# 04_CONNECTOR_OUT_2.net
KiCad netlist of a schematic drawn in Altium Designer
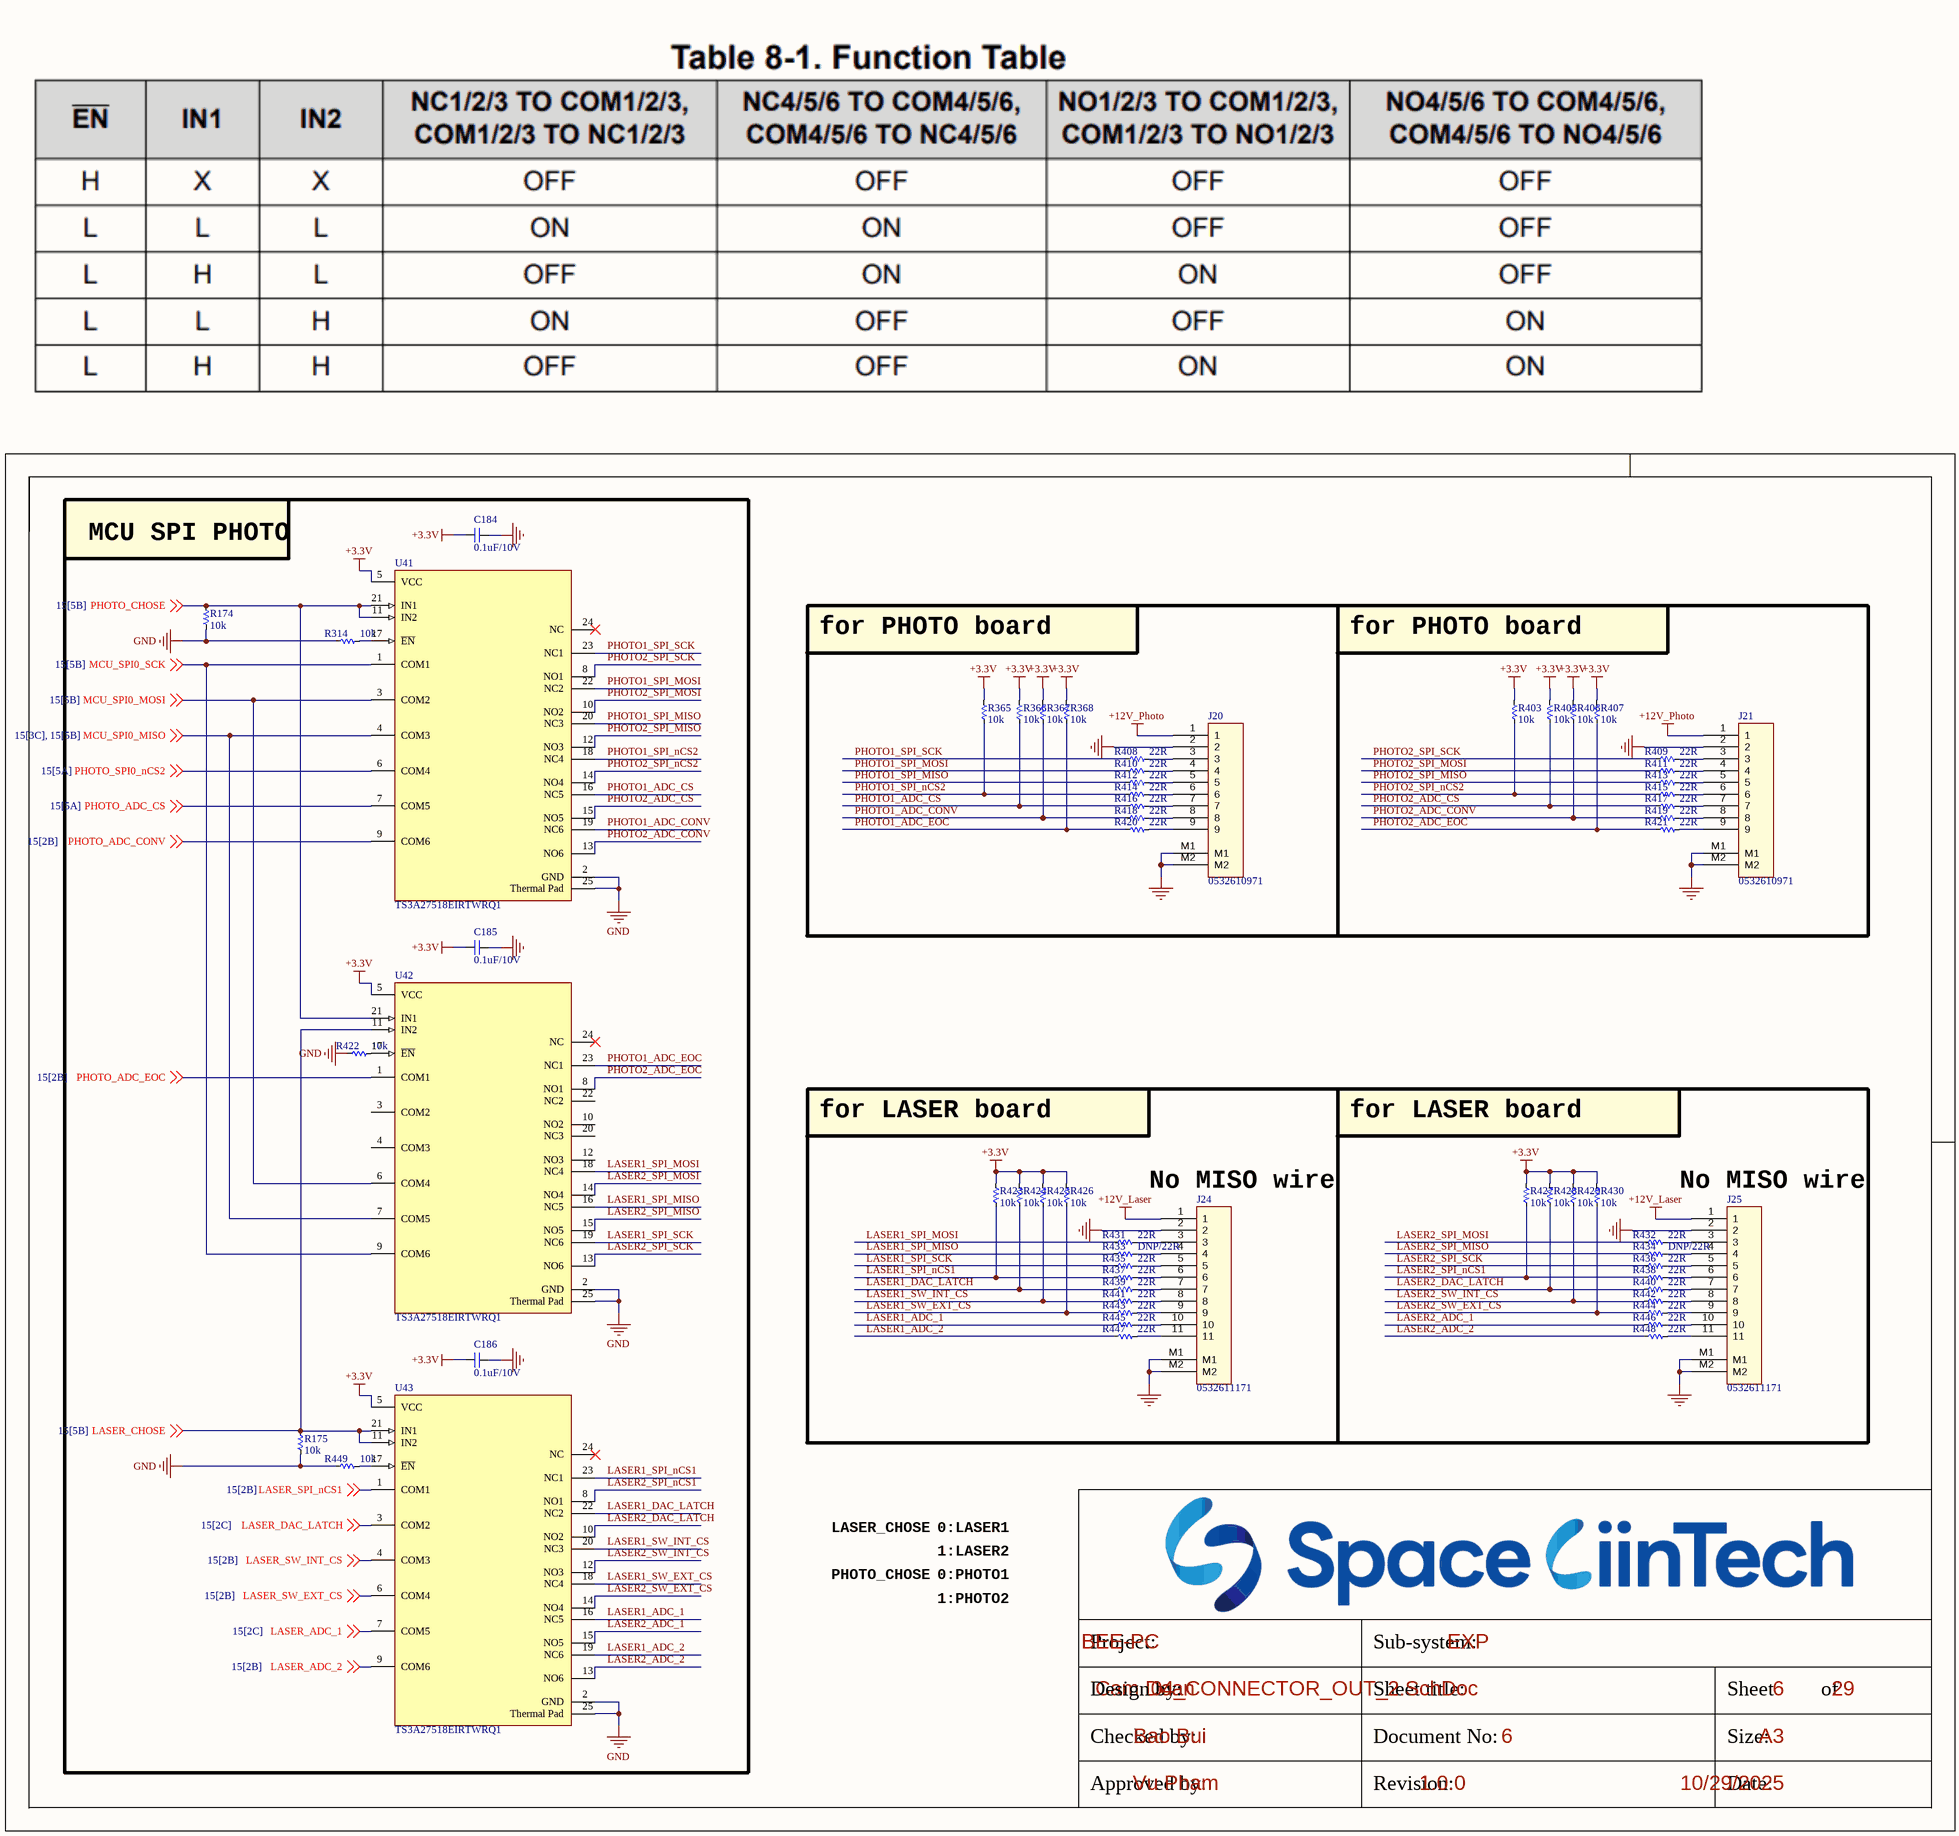
[diagram p0: 04_CONNECTOR_OUT_2.SchDoc]

(export (version "E")
  (design (tool "Eeschema 10.0.6"))
  (components
    (comp (ref "C184")
      (value "0.1uF/10V")
      (footprint "CAP_C_1005X60")
      (description "CAP CHIP")
      (libsource (lib "LABLIB") (part "_CAP_C_2"))
    )
    (comp (ref "C185")
      (value "0.1uF/10V")
      (footprint "CAP_C_1005X60")
      (description "CAP CHIP")
      (libsource (lib "LABLIB") (part "_CAP_C_2"))
    )
    (comp (ref "C186")
      (value "0.1uF/10V")
      (footprint "CAP_C_1005X60")
      (description "CAP CHIP")
      (libsource (lib "LABLIB") (part "_CAP_C_2"))
    )
    (comp (ref "J20")
      (value "0532610971")
      (footprint "MOLEX_0532610971")
      (libsource (lib "LABLIB") (part "Header 9x1_2M"))
    )
    (comp (ref "J21")
      (value "0532610971")
      (footprint "MOLEX_0532610971")
      (libsource (lib "LABLIB") (part "Header 9x1_2M"))
    )
    (comp (ref "J24")
      (value "0532611171")
      (footprint "MOLEX_0532611171")
      (libsource (lib "LABLIB") (part "Header 11x1_2M"))
    )
    (comp (ref "J25")
      (value "0532611171")
      (footprint "MOLEX_0532611171")
      (libsource (lib "LABLIB") (part "Header 11x1_2M"))
    )
    (comp (ref "R174")
      (value "10k")
      (footprint "RES_C_1005X40")
      (description "RES")
      (libsource (lib "LABLIB") (part "_RES_B_2"))
    )
    (comp (ref "R175")
      (value "10k")
      (footprint "RES_C_1005X40")
      (description "RES")
      (libsource (lib "LABLIB") (part "_RES_B_2"))
    )
    (comp (ref "R314")
      (value "10k")
      (footprint "RES_C_1005X40")
      (description "RES")
      (libsource (lib "LABLIB") (part "_RES_B_2"))
    )
    (comp (ref "R365")
      (value "10k")
      (footprint "RES_C_1005X40")
      (description "RES")
      (libsource (lib "LABLIB") (part "_RES_B_2"))
    )
    (comp (ref "R366")
      (value "10k")
      (footprint "RES_C_1005X40")
      (description "RES")
      (libsource (lib "LABLIB") (part "_RES_B_2"))
    )
    (comp (ref "R367")
      (value "10k")
      (footprint "RES_C_1005X40")
      (description "RES")
      (libsource (lib "LABLIB") (part "_RES_B_2"))
    )
    (comp (ref "R368")
      (value "10k")
      (footprint "RES_C_1005X40")
      (description "RES")
      (libsource (lib "LABLIB") (part "_RES_B_2"))
    )
    (comp (ref "R403")
      (value "10k")
      (footprint "RES_C_1005X40")
      (description "RES")
      (libsource (lib "LABLIB") (part "_RES_B_2"))
    )
    (comp (ref "R405")
      (value "10k")
      (footprint "RES_C_1005X40")
      (description "RES")
      (libsource (lib "LABLIB") (part "_RES_B_2"))
    )
    (comp (ref "R406")
      (value "10k")
      (footprint "RES_C_1005X40")
      (description "RES")
      (libsource (lib "LABLIB") (part "_RES_B_2"))
    )
    (comp (ref "R407")
      (value "10k")
      (footprint "RES_C_1005X40")
      (description "RES")
      (libsource (lib "LABLIB") (part "_RES_B_2"))
    )
    (comp (ref "R408")
      (value "22R")
      (footprint "RES_C_1005X40")
      (description "RES")
      (libsource (lib "LABLIB") (part "_RES_B_2"))
    )
    (comp (ref "R409")
      (value "22R")
      (footprint "RES_C_1005X40")
      (description "RES")
      (libsource (lib "LABLIB") (part "_RES_B_2"))
    )
    (comp (ref "R410")
      (value "22R")
      (footprint "RES_C_1005X40")
      (description "RES")
      (libsource (lib "LABLIB") (part "_RES_B_2"))
    )
    (comp (ref "R411")
      (value "22R")
      (footprint "RES_C_1005X40")
      (description "RES")
      (libsource (lib "LABLIB") (part "_RES_B_2"))
    )
    (comp (ref "R412")
      (value "22R")
      (footprint "RES_C_1005X40")
      (description "RES")
      (libsource (lib "LABLIB") (part "_RES_B_2"))
    )
    (comp (ref "R413")
      (value "22R")
      (footprint "RES_C_1005X40")
      (description "RES")
      (libsource (lib "LABLIB") (part "_RES_B_2"))
    )
    (comp (ref "R414")
      (value "22R")
      (footprint "RES_C_1005X40")
      (description "RES")
      (libsource (lib "LABLIB") (part "_RES_B_2"))
    )
    (comp (ref "R415")
      (value "22R")
      (footprint "RES_C_1005X40")
      (description "RES")
      (libsource (lib "LABLIB") (part "_RES_B_2"))
    )
    (comp (ref "R416")
      (value "22R")
      (footprint "RES_C_1005X40")
      (description "RES")
      (libsource (lib "LABLIB") (part "_RES_B_2"))
    )
    (comp (ref "R417")
      (value "22R")
      (footprint "RES_C_1005X40")
      (description "RES")
      (libsource (lib "LABLIB") (part "_RES_B_2"))
    )
    (comp (ref "R418")
      (value "22R")
      (footprint "RES_C_1005X40")
      (description "RES")
      (libsource (lib "LABLIB") (part "_RES_B_2"))
    )
    (comp (ref "R419")
      (value "22R")
      (footprint "RES_C_1005X40")
      (description "RES")
      (libsource (lib "LABLIB") (part "_RES_B_2"))
    )
    (comp (ref "R420")
      (value "22R")
      (footprint "RES_C_1005X40")
      (description "RES")
      (libsource (lib "LABLIB") (part "_RES_B_2"))
    )
    (comp (ref "R421")
      (value "22R")
      (footprint "RES_C_1005X40")
      (description "RES")
      (libsource (lib "LABLIB") (part "_RES_B_2"))
    )
    (comp (ref "R422")
      (value "10k")
      (footprint "RES_C_1005X40")
      (description "RES")
      (libsource (lib "LABLIB") (part "_RES_B_2"))
    )
    (comp (ref "R423")
      (value "10k")
      (footprint "RES_C_1005X40")
      (description "RES")
      (libsource (lib "LABLIB") (part "_RES_B_2"))
    )
    (comp (ref "R424")
      (value "10k")
      (footprint "RES_C_1005X40")
      (description "RES")
      (libsource (lib "LABLIB") (part "_RES_B_2"))
    )
    (comp (ref "R425")
      (value "10k")
      (footprint "RES_C_1005X40")
      (description "RES")
      (libsource (lib "LABLIB") (part "_RES_B_2"))
    )
    (comp (ref "R426")
      (value "10k")
      (footprint "RES_C_1005X40")
      (description "RES")
      (libsource (lib "LABLIB") (part "_RES_B_2"))
    )
    (comp (ref "R427")
      (value "10k")
      (footprint "RES_C_1005X40")
      (description "RES")
      (libsource (lib "LABLIB") (part "_RES_B_2"))
    )
    (comp (ref "R428")
      (value "10k")
      (footprint "RES_C_1005X40")
      (description "RES")
      (libsource (lib "LABLIB") (part "_RES_B_2"))
    )
    (comp (ref "R429")
      (value "10k")
      (footprint "RES_C_1005X40")
      (description "RES")
      (libsource (lib "LABLIB") (part "_RES_B_2"))
    )
    (comp (ref "R430")
      (value "10k")
      (footprint "RES_C_1005X40")
      (description "RES")
      (libsource (lib "LABLIB") (part "_RES_B_2"))
    )
    (comp (ref "R431")
      (value "22R")
      (footprint "RES_C_1005X40")
      (description "RES")
      (libsource (lib "LABLIB") (part "_RES_B_2"))
    )
    (comp (ref "R432")
      (value "22R")
      (footprint "RES_C_1005X40")
      (description "RES")
      (libsource (lib "LABLIB") (part "_RES_B_2"))
    )
    (comp (ref "R433")
      (value "DNP/22R")
      (footprint "RES_C_1005X40")
      (description "RES")
      (libsource (lib "LABLIB") (part "_RES_B_2"))
    )
    (comp (ref "R434")
      (value "DNP/22R")
      (footprint "RES_C_1005X40")
      (description "RES")
      (libsource (lib "LABLIB") (part "_RES_B_2"))
    )
    (comp (ref "R435")
      (value "22R")
      (footprint "RES_C_1005X40")
      (description "RES")
      (libsource (lib "LABLIB") (part "_RES_B_2"))
    )
    (comp (ref "R436")
      (value "22R")
      (footprint "RES_C_1005X40")
      (description "RES")
      (libsource (lib "LABLIB") (part "_RES_B_2"))
    )
    (comp (ref "R437")
      (value "22R")
      (footprint "RES_C_1005X40")
      (description "RES")
      (libsource (lib "LABLIB") (part "_RES_B_2"))
    )
    (comp (ref "R438")
      (value "22R")
      (footprint "RES_C_1005X40")
      (description "RES")
      (libsource (lib "LABLIB") (part "_RES_B_2"))
    )
    (comp (ref "R439")
      (value "22R")
      (footprint "RES_C_1005X40")
      (description "RES")
      (libsource (lib "LABLIB") (part "_RES_B_2"))
    )
    (comp (ref "R440")
      (value "22R")
      (footprint "RES_C_1005X40")
      (description "RES")
      (libsource (lib "LABLIB") (part "_RES_B_2"))
    )
    (comp (ref "R441")
      (value "22R")
      (footprint "RES_C_1005X40")
      (description "RES")
      (libsource (lib "LABLIB") (part "_RES_B_2"))
    )
    (comp (ref "R442")
      (value "22R")
      (footprint "RES_C_1005X40")
      (description "RES")
      (libsource (lib "LABLIB") (part "_RES_B_2"))
    )
    (comp (ref "R443")
      (value "22R")
      (footprint "RES_C_1005X40")
      (description "RES")
      (libsource (lib "LABLIB") (part "_RES_B_2"))
    )
    (comp (ref "R444")
      (value "22R")
      (footprint "RES_C_1005X40")
      (description "RES")
      (libsource (lib "LABLIB") (part "_RES_B_2"))
    )
    (comp (ref "R445")
      (value "22R")
      (footprint "RES_C_1005X40")
      (description "RES")
      (libsource (lib "LABLIB") (part "_RES_B_2"))
    )
    (comp (ref "R446")
      (value "22R")
      (footprint "RES_C_1005X40")
      (description "RES")
      (libsource (lib "LABLIB") (part "_RES_B_2"))
    )
    (comp (ref "R447")
      (value "22R")
      (footprint "RES_C_1005X40")
      (description "RES")
      (libsource (lib "LABLIB") (part "_RES_B_2"))
    )
    (comp (ref "R448")
      (value "22R")
      (footprint "RES_C_1005X40")
      (description "RES")
      (libsource (lib "LABLIB") (part "_RES_B_2"))
    )
    (comp (ref "R449")
      (value "10k")
      (footprint "RES_C_1005X40")
      (description "RES")
      (libsource (lib "LABLIB") (part "_RES_B_2"))
    )
    (comp (ref "U41")
      (value "TS3A27518EIRTWRQ1")
      (footprint "FP-RTW0024B-IPC_A")
      (description "IC MUX/DEMUX 1X2 24WQFN")
      (libsource (lib "Altium Content Vault") (part "ff327f4631d6a819810aeca967572ba"))
    )
    (comp (ref "U42")
      (value "TS3A27518EIRTWRQ1")
      (footprint "FP-RTW0024B-IPC_A")
      (description "IC MUX/DEMUX 1X2 24WQFN")
      (libsource (lib "Altium Content Vault") (part "ff327f4631d6a819810aeca967572ba"))
    )
    (comp (ref "U43")
      (value "TS3A27518EIRTWRQ1")
      (footprint "FP-RTW0024B-IPC_A")
      (description "IC MUX/DEMUX 1X2 24WQFN")
      (libsource (lib "Altium Content Vault") (part "ff327f4631d6a819810aeca967572ba"))
    )
  )
  (nets
    (net (code "1") (name "+3.3V") (class "Default")
      (node (ref "C184") (pin "2") (pinfunction "2_2") (pintype "passive"))
      (node (ref "C185") (pin "2") (pinfunction "2_2") (pintype "passive"))
      (node (ref "C186") (pin "2") (pinfunction "2_2") (pintype "passive"))
      (node (ref "R365") (pin "1") (pinfunction "1_1") (pintype "passive"))
      (node (ref "R366") (pin "1") (pinfunction "1_1") (pintype "passive"))
      (node (ref "R367") (pin "1") (pinfunction "1_1") (pintype "passive"))
      (node (ref "R368") (pin "1") (pinfunction "1_1") (pintype "passive"))
      (node (ref "R403") (pin "1") (pinfunction "1_1") (pintype "passive"))
      (node (ref "R405") (pin "1") (pinfunction "1_1") (pintype "passive"))
      (node (ref "R406") (pin "1") (pinfunction "1_1") (pintype "passive"))
      (node (ref "R407") (pin "1") (pinfunction "1_1") (pintype "passive"))
      (node (ref "R423") (pin "1") (pinfunction "1_1") (pintype "passive"))
      (node (ref "R424") (pin "1") (pinfunction "1_1") (pintype "passive"))
      (node (ref "R425") (pin "1") (pinfunction "1_1") (pintype "passive"))
      (node (ref "R426") (pin "1") (pinfunction "1_1") (pintype "passive"))
      (node (ref "R427") (pin "1") (pinfunction "1_1") (pintype "passive"))
      (node (ref "R428") (pin "1") (pinfunction "1_1") (pintype "passive"))
      (node (ref "R429") (pin "1") (pinfunction "1_1") (pintype "passive"))
      (node (ref "R430") (pin "1") (pinfunction "1_1") (pintype "passive"))
      (node (ref "U41") (pin "5") (pinfunction "VCC_5") (pintype "power_in"))
      (node (ref "U42") (pin "5") (pinfunction "VCC_5") (pintype "power_in"))
      (node (ref "U43") (pin "5") (pinfunction "VCC_5") (pintype "power_in"))
    )
    (net (code "2") (name "+12V_Laser") (class "Default")
      (node (ref "J24") (pin "1") (pinfunction "1_1") (pintype "passive"))
      (node (ref "J25") (pin "1") (pinfunction "1_1") (pintype "passive"))
    )
    (net (code "3") (name "+12V_Photo") (class "Default")
      (node (ref "J20") (pin "1") (pinfunction "1_1") (pintype "passive"))
      (node (ref "J21") (pin "1") (pinfunction "1_1") (pintype "passive"))
    )
    (net (code "4") (name "/LASER1_ADC_1") (class "Default")
      (node (ref "R445") (pin "1") (pinfunction "1_1") (pintype "passive"))
      (node (ref "U43") (pin "16") (pinfunction "NC5_16") (pintype "passive"))
    )
    (net (code "5") (name "/LASER1_ADC_2") (class "Default")
      (node (ref "R447") (pin "1") (pinfunction "1_1") (pintype "passive"))
      (node (ref "U43") (pin "19") (pinfunction "NC6_19") (pintype "passive"))
    )
    (net (code "6") (name "/LASER1_DAC_LATCH") (class "Default")
      (node (ref "R424") (pin "2") (pinfunction "2_2") (pintype "passive"))
      (node (ref "R439") (pin "1") (pinfunction "1_1") (pintype "passive"))
      (node (ref "U43") (pin "22") (pinfunction "NC2_22") (pintype "passive"))
    )
    (net (code "7") (name "/LASER1_SPI_MISO") (class "Default")
      (node (ref "R433") (pin "1") (pinfunction "1_1") (pintype "passive"))
      (node (ref "U42") (pin "16") (pinfunction "NC5_16") (pintype "passive"))
    )
    (net (code "8") (name "/LASER1_SPI_MOSI") (class "Default")
      (node (ref "R431") (pin "1") (pinfunction "1_1") (pintype "passive"))
      (node (ref "U42") (pin "18") (pinfunction "NC4_18") (pintype "passive"))
    )
    (net (code "9") (name "/LASER1_SPI_SCK") (class "Default")
      (node (ref "R435") (pin "1") (pinfunction "1_1") (pintype "passive"))
      (node (ref "U42") (pin "19") (pinfunction "NC6_19") (pintype "passive"))
    )
    (net (code "10") (name "/LASER1_SPI_nCS1") (class "Default")
      (node (ref "R423") (pin "2") (pinfunction "2_2") (pintype "passive"))
      (node (ref "R437") (pin "1") (pinfunction "1_1") (pintype "passive"))
      (node (ref "U43") (pin "23") (pinfunction "NC1_23") (pintype "passive"))
    )
    (net (code "11") (name "/LASER1_SW_EXT_CS") (class "Default")
      (node (ref "R426") (pin "2") (pinfunction "2_2") (pintype "passive"))
      (node (ref "R443") (pin "1") (pinfunction "1_1") (pintype "passive"))
      (node (ref "U43") (pin "18") (pinfunction "NC4_18") (pintype "passive"))
    )
    (net (code "12") (name "/LASER1_SW_INT_CS") (class "Default")
      (node (ref "R425") (pin "2") (pinfunction "2_2") (pintype "passive"))
      (node (ref "R441") (pin "1") (pinfunction "1_1") (pintype "passive"))
      (node (ref "U43") (pin "20") (pinfunction "NC3_20") (pintype "passive"))
    )
    (net (code "13") (name "/LASER2_ADC_1") (class "Default")
      (node (ref "R446") (pin "1") (pinfunction "1_1") (pintype "passive"))
      (node (ref "U43") (pin "15") (pinfunction "NO5_15") (pintype "passive"))
    )
    (net (code "14") (name "/LASER2_ADC_2") (class "Default")
      (node (ref "R448") (pin "1") (pinfunction "1_1") (pintype "passive"))
      (node (ref "U43") (pin "13") (pinfunction "NO6_13") (pintype "passive"))
    )
    (net (code "15") (name "/LASER2_DAC_LATCH") (class "Default")
      (node (ref "R428") (pin "2") (pinfunction "2_2") (pintype "passive"))
      (node (ref "R440") (pin "1") (pinfunction "1_1") (pintype "passive"))
      (node (ref "U43") (pin "10") (pinfunction "NO2_10") (pintype "passive"))
    )
    (net (code "16") (name "/LASER2_SPI_MISO") (class "Default")
      (node (ref "R434") (pin "1") (pinfunction "1_1") (pintype "passive"))
      (node (ref "U42") (pin "15") (pinfunction "NO5_15") (pintype "passive"))
    )
    (net (code "17") (name "/LASER2_SPI_MOSI") (class "Default")
      (node (ref "R432") (pin "1") (pinfunction "1_1") (pintype "passive"))
      (node (ref "U42") (pin "14") (pinfunction "NO4_14") (pintype "passive"))
    )
    (net (code "18") (name "/LASER2_SPI_SCK") (class "Default")
      (node (ref "R436") (pin "1") (pinfunction "1_1") (pintype "passive"))
      (node (ref "U42") (pin "13") (pinfunction "NO6_13") (pintype "passive"))
    )
    (net (code "19") (name "/LASER2_SPI_nCS1") (class "Default")
      (node (ref "R427") (pin "2") (pinfunction "2_2") (pintype "passive"))
      (node (ref "R438") (pin "1") (pinfunction "1_1") (pintype "passive"))
      (node (ref "U43") (pin "8") (pinfunction "NO1_8") (pintype "passive"))
    )
    (net (code "20") (name "/LASER2_SW_EXT_CS") (class "Default")
      (node (ref "R430") (pin "2") (pinfunction "2_2") (pintype "passive"))
      (node (ref "R444") (pin "1") (pinfunction "1_1") (pintype "passive"))
      (node (ref "U43") (pin "14") (pinfunction "NO4_14") (pintype "passive"))
    )
    (net (code "21") (name "/LASER2_SW_INT_CS") (class "Default")
      (node (ref "R429") (pin "2") (pinfunction "2_2") (pintype "passive"))
      (node (ref "R442") (pin "1") (pinfunction "1_1") (pintype "passive"))
      (node (ref "U43") (pin "12") (pinfunction "NO3_12") (pintype "passive"))
    )
    (net (code "22") (name "/PHOTO1_ADC_CONV") (class "Default")
      (node (ref "R367") (pin "2") (pinfunction "2_2") (pintype "passive"))
      (node (ref "R418") (pin "1") (pinfunction "1_1") (pintype "passive"))
      (node (ref "U41") (pin "19") (pinfunction "NC6_19") (pintype "passive"))
    )
    (net (code "23") (name "/PHOTO1_ADC_CS") (class "Default")
      (node (ref "R366") (pin "2") (pinfunction "2_2") (pintype "passive"))
      (node (ref "R416") (pin "1") (pinfunction "1_1") (pintype "passive"))
      (node (ref "U41") (pin "16") (pinfunction "NC5_16") (pintype "passive"))
    )
    (net (code "24") (name "/PHOTO1_ADC_EOC") (class "Default")
      (node (ref "R368") (pin "2") (pinfunction "2_2") (pintype "passive"))
      (node (ref "R420") (pin "1") (pinfunction "1_1") (pintype "passive"))
      (node (ref "U42") (pin "23") (pinfunction "NC1_23") (pintype "passive"))
    )
    (net (code "25") (name "/PHOTO1_SPI_MISO") (class "Default")
      (node (ref "R412") (pin "1") (pinfunction "1_1") (pintype "passive"))
      (node (ref "U41") (pin "20") (pinfunction "NC3_20") (pintype "passive"))
    )
    (net (code "26") (name "/PHOTO1_SPI_MOSI") (class "Default")
      (node (ref "R410") (pin "1") (pinfunction "1_1") (pintype "passive"))
      (node (ref "U41") (pin "22") (pinfunction "NC2_22") (pintype "passive"))
    )
    (net (code "27") (name "/PHOTO1_SPI_SCK") (class "Default")
      (node (ref "R408") (pin "1") (pinfunction "1_1") (pintype "passive"))
      (node (ref "U41") (pin "23") (pinfunction "NC1_23") (pintype "passive"))
    )
    (net (code "28") (name "/PHOTO1_SPI_nCS2") (class "Default")
      (node (ref "R365") (pin "2") (pinfunction "2_2") (pintype "passive"))
      (node (ref "R414") (pin "1") (pinfunction "1_1") (pintype "passive"))
      (node (ref "U41") (pin "18") (pinfunction "NC4_18") (pintype "passive"))
    )
    (net (code "29") (name "/PHOTO2_ADC_CONV") (class "Default")
      (node (ref "R406") (pin "2") (pinfunction "2_2") (pintype "passive"))
      (node (ref "R419") (pin "1") (pinfunction "1_1") (pintype "passive"))
      (node (ref "U41") (pin "13") (pinfunction "NO6_13") (pintype "passive"))
    )
    (net (code "30") (name "/PHOTO2_ADC_CS") (class "Default")
      (node (ref "R405") (pin "2") (pinfunction "2_2") (pintype "passive"))
      (node (ref "R417") (pin "1") (pinfunction "1_1") (pintype "passive"))
      (node (ref "U41") (pin "15") (pinfunction "NO5_15") (pintype "passive"))
    )
    (net (code "31") (name "/PHOTO2_ADC_EOC") (class "Default")
      (node (ref "R407") (pin "2") (pinfunction "2_2") (pintype "passive"))
      (node (ref "R421") (pin "1") (pinfunction "1_1") (pintype "passive"))
      (node (ref "U42") (pin "8") (pinfunction "NO1_8") (pintype "passive"))
    )
    (net (code "32") (name "/PHOTO2_SPI_MISO") (class "Default")
      (node (ref "R413") (pin "1") (pinfunction "1_1") (pintype "passive"))
      (node (ref "U41") (pin "12") (pinfunction "NO3_12") (pintype "passive"))
    )
    (net (code "33") (name "/PHOTO2_SPI_MOSI") (class "Default")
      (node (ref "R411") (pin "1") (pinfunction "1_1") (pintype "passive"))
      (node (ref "U41") (pin "10") (pinfunction "NO2_10") (pintype "passive"))
    )
    (net (code "34") (name "/PHOTO2_SPI_SCK") (class "Default")
      (node (ref "R409") (pin "1") (pinfunction "1_1") (pintype "passive"))
      (node (ref "U41") (pin "8") (pinfunction "NO1_8") (pintype "passive"))
    )
    (net (code "35") (name "/PHOTO2_SPI_nCS2") (class "Default")
      (node (ref "R403") (pin "2") (pinfunction "2_2") (pintype "passive"))
      (node (ref "R415") (pin "1") (pinfunction "1_1") (pintype "passive"))
      (node (ref "U41") (pin "14") (pinfunction "NO4_14") (pintype "passive"))
    )
    (net (code "36") (name "GND") (class "Default")
      (node (ref "C184") (pin "1") (pinfunction "1_1") (pintype "passive"))
      (node (ref "C185") (pin "1") (pinfunction "1_1") (pintype "passive"))
      (node (ref "C186") (pin "1") (pinfunction "1_1") (pintype "passive"))
      (node (ref "J20") (pin "2") (pinfunction "2_2") (pintype "passive"))
      (node (ref "J20") (pin "M1") (pinfunction "M1_M1") (pintype "passive"))
      (node (ref "J20") (pin "M2") (pinfunction "M2_M2") (pintype "passive"))
      (node (ref "J21") (pin "2") (pinfunction "2_2") (pintype "passive"))
      (node (ref "J21") (pin "M1") (pinfunction "M1_M1") (pintype "passive"))
      (node (ref "J21") (pin "M2") (pinfunction "M2_M2") (pintype "passive"))
      (node (ref "J24") (pin "2") (pinfunction "2_2") (pintype "passive"))
      (node (ref "J24") (pin "M1") (pinfunction "M1_M1") (pintype "passive"))
      (node (ref "J24") (pin "M2") (pinfunction "M2_M2") (pintype "passive"))
      (node (ref "J25") (pin "2") (pinfunction "2_2") (pintype "passive"))
      (node (ref "J25") (pin "M1") (pinfunction "M1_M1") (pintype "passive"))
      (node (ref "J25") (pin "M2") (pinfunction "M2_M2") (pintype "passive"))
      (node (ref "R174") (pin "1") (pinfunction "1_1") (pintype "passive"))
      (node (ref "R175") (pin "1") (pinfunction "1_1") (pintype "passive"))
      (node (ref "R314") (pin "1") (pinfunction "1_1") (pintype "passive"))
      (node (ref "R422") (pin "1") (pinfunction "1_1") (pintype "passive"))
      (node (ref "R449") (pin "1") (pinfunction "1_1") (pintype "passive"))
      (node (ref "U41") (pin "2") (pinfunction "GND_2") (pintype "power_in"))
      (node (ref "U41") (pin "25") (pinfunction "Thermal_Pad_25") (pintype "power_in"))
      (node (ref "U42") (pin "2") (pinfunction "GND_2") (pintype "power_in"))
      (node (ref "U42") (pin "25") (pinfunction "Thermal_Pad_25") (pintype "power_in"))
      (node (ref "U43") (pin "2") (pinfunction "GND_2") (pintype "power_in"))
      (node (ref "U43") (pin "25") (pinfunction "Thermal_Pad_25") (pintype "power_in"))
    )
    (net (code "37") (name "LASER_ADC_1") (class "Default")
      (node (ref "U43") (pin "7") (pinfunction "COM5_7") (pintype "passive"))
    )
    (net (code "38") (name "LASER_ADC_2") (class "Default")
      (node (ref "U43") (pin "9") (pinfunction "COM6_9") (pintype "passive"))
    )
    (net (code "39") (name "LASER_CHOSE") (class "Default")
      (node (ref "R175") (pin "2") (pinfunction "2_2") (pintype "passive"))
      (node (ref "U42") (pin "11") (pinfunction "IN2_11") (pintype "input"))
      (node (ref "U43") (pin "11") (pinfunction "IN2_11") (pintype "input"))
      (node (ref "U43") (pin "21") (pinfunction "IN1_21") (pintype "input"))
    )
    (net (code "40") (name "LASER_DAC_LATCH") (class "Default")
      (node (ref "U43") (pin "3") (pinfunction "COM2_3") (pintype "passive"))
    )
    (net (code "41") (name "LASER_SPI_nCS1") (class "Default")
      (node (ref "U43") (pin "1") (pinfunction "COM1_1") (pintype "passive"))
    )
    (net (code "42") (name "LASER_SW_EXT_CS") (class "Default")
      (node (ref "U43") (pin "6") (pinfunction "COM4_6") (pintype "passive"))
    )
    (net (code "43") (name "LASER_SW_INT_CS") (class "Default")
      (node (ref "U43") (pin "4") (pinfunction "COM3_4") (pintype "passive"))
    )
    (net (code "44") (name "MCU_SPI0_MISO") (class "Default")
      (node (ref "U41") (pin "4") (pinfunction "COM3_4") (pintype "passive"))
      (node (ref "U42") (pin "7") (pinfunction "COM5_7") (pintype "passive"))
    )
    (net (code "45") (name "MCU_SPI0_MOSI") (class "Default")
      (node (ref "U41") (pin "3") (pinfunction "COM2_3") (pintype "passive"))
      (node (ref "U42") (pin "6") (pinfunction "COM4_6") (pintype "passive"))
    )
    (net (code "46") (name "MCU_SPI0_SCK") (class "Default")
      (node (ref "U41") (pin "1") (pinfunction "COM1_1") (pintype "passive"))
      (node (ref "U42") (pin "9") (pinfunction "COM6_9") (pintype "passive"))
    )
    (net (code "47") (name "Net-(J20-Pad3)") (class "Default")
      (node (ref "J20") (pin "3") (pinfunction "3_3") (pintype "passive"))
      (node (ref "R408") (pin "2") (pinfunction "2_2") (pintype "passive"))
    )
    (net (code "48") (name "Net-(J20-Pad4)") (class "Default")
      (node (ref "J20") (pin "4") (pinfunction "4_4") (pintype "passive"))
      (node (ref "R410") (pin "2") (pinfunction "2_2") (pintype "passive"))
    )
    (net (code "49") (name "Net-(J20-Pad5)") (class "Default")
      (node (ref "J20") (pin "5") (pinfunction "5_5") (pintype "passive"))
      (node (ref "R412") (pin "2") (pinfunction "2_2") (pintype "passive"))
    )
    (net (code "50") (name "Net-(J20-Pad6)") (class "Default")
      (node (ref "J20") (pin "6") (pinfunction "6_6") (pintype "passive"))
      (node (ref "R414") (pin "2") (pinfunction "2_2") (pintype "passive"))
    )
    (net (code "51") (name "Net-(J20-Pad7)") (class "Default")
      (node (ref "J20") (pin "7") (pinfunction "7_7") (pintype "passive"))
      (node (ref "R416") (pin "2") (pinfunction "2_2") (pintype "passive"))
    )
    (net (code "52") (name "Net-(J20-Pad8)") (class "Default")
      (node (ref "J20") (pin "8") (pinfunction "8_8") (pintype "passive"))
      (node (ref "R418") (pin "2") (pinfunction "2_2") (pintype "passive"))
    )
    (net (code "53") (name "Net-(J20-Pad9)") (class "Default")
      (node (ref "J20") (pin "9") (pinfunction "9_9") (pintype "passive"))
      (node (ref "R420") (pin "2") (pinfunction "2_2") (pintype "passive"))
    )
    (net (code "54") (name "Net-(J21-Pad3)") (class "Default")
      (node (ref "J21") (pin "3") (pinfunction "3_3") (pintype "passive"))
      (node (ref "R409") (pin "2") (pinfunction "2_2") (pintype "passive"))
    )
    (net (code "55") (name "Net-(J21-Pad4)") (class "Default")
      (node (ref "J21") (pin "4") (pinfunction "4_4") (pintype "passive"))
      (node (ref "R411") (pin "2") (pinfunction "2_2") (pintype "passive"))
    )
    (net (code "56") (name "Net-(J21-Pad5)") (class "Default")
      (node (ref "J21") (pin "5") (pinfunction "5_5") (pintype "passive"))
      (node (ref "R413") (pin "2") (pinfunction "2_2") (pintype "passive"))
    )
    (net (code "57") (name "Net-(J21-Pad6)") (class "Default")
      (node (ref "J21") (pin "6") (pinfunction "6_6") (pintype "passive"))
      (node (ref "R415") (pin "2") (pinfunction "2_2") (pintype "passive"))
    )
    (net (code "58") (name "Net-(J21-Pad7)") (class "Default")
      (node (ref "J21") (pin "7") (pinfunction "7_7") (pintype "passive"))
      (node (ref "R417") (pin "2") (pinfunction "2_2") (pintype "passive"))
    )
    (net (code "59") (name "Net-(J21-Pad8)") (class "Default")
      (node (ref "J21") (pin "8") (pinfunction "8_8") (pintype "passive"))
      (node (ref "R419") (pin "2") (pinfunction "2_2") (pintype "passive"))
    )
    (net (code "60") (name "Net-(J21-Pad9)") (class "Default")
      (node (ref "J21") (pin "9") (pinfunction "9_9") (pintype "passive"))
      (node (ref "R421") (pin "2") (pinfunction "2_2") (pintype "passive"))
    )
    (net (code "61") (name "Net-(J24-Pad3)") (class "Default")
      (node (ref "J24") (pin "3") (pinfunction "3_3") (pintype "passive"))
      (node (ref "R431") (pin "2") (pinfunction "2_2") (pintype "passive"))
    )
    (net (code "62") (name "Net-(J24-Pad4)") (class "Default")
      (node (ref "J24") (pin "4") (pinfunction "4_4") (pintype "passive"))
      (node (ref "R433") (pin "2") (pinfunction "2_2") (pintype "passive"))
    )
    (net (code "63") (name "Net-(J24-Pad5)") (class "Default")
      (node (ref "J24") (pin "5") (pinfunction "5_5") (pintype "passive"))
      (node (ref "R435") (pin "2") (pinfunction "2_2") (pintype "passive"))
    )
    (net (code "64") (name "Net-(J24-Pad6)") (class "Default")
      (node (ref "J24") (pin "6") (pinfunction "6_6") (pintype "passive"))
      (node (ref "R437") (pin "2") (pinfunction "2_2") (pintype "passive"))
    )
    (net (code "65") (name "Net-(J24-Pad7)") (class "Default")
      (node (ref "J24") (pin "7") (pinfunction "7_7") (pintype "passive"))
      (node (ref "R439") (pin "2") (pinfunction "2_2") (pintype "passive"))
    )
    (net (code "66") (name "Net-(J24-Pad8)") (class "Default")
      (node (ref "J24") (pin "8") (pinfunction "8_8") (pintype "passive"))
      (node (ref "R441") (pin "2") (pinfunction "2_2") (pintype "passive"))
    )
    (net (code "67") (name "Net-(J24-Pad9)") (class "Default")
      (node (ref "J24") (pin "9") (pinfunction "9_9") (pintype "passive"))
      (node (ref "R443") (pin "2") (pinfunction "2_2") (pintype "passive"))
    )
    (net (code "68") (name "Net-(J24-Pad10)") (class "Default")
      (node (ref "J24") (pin "10") (pinfunction "10_10") (pintype "passive"))
      (node (ref "R445") (pin "2") (pinfunction "2_2") (pintype "passive"))
    )
    (net (code "69") (name "Net-(J24-Pad11)") (class "Default")
      (node (ref "J24") (pin "11") (pinfunction "11_11") (pintype "passive"))
      (node (ref "R447") (pin "2") (pinfunction "2_2") (pintype "passive"))
    )
    (net (code "70") (name "Net-(J25-Pad3)") (class "Default")
      (node (ref "J25") (pin "3") (pinfunction "3_3") (pintype "passive"))
      (node (ref "R432") (pin "2") (pinfunction "2_2") (pintype "passive"))
    )
    (net (code "71") (name "Net-(J25-Pad4)") (class "Default")
      (node (ref "J25") (pin "4") (pinfunction "4_4") (pintype "passive"))
      (node (ref "R434") (pin "2") (pinfunction "2_2") (pintype "passive"))
    )
    (net (code "72") (name "Net-(J25-Pad5)") (class "Default")
      (node (ref "J25") (pin "5") (pinfunction "5_5") (pintype "passive"))
      (node (ref "R436") (pin "2") (pinfunction "2_2") (pintype "passive"))
    )
    (net (code "73") (name "Net-(J25-Pad6)") (class "Default")
      (node (ref "J25") (pin "6") (pinfunction "6_6") (pintype "passive"))
      (node (ref "R438") (pin "2") (pinfunction "2_2") (pintype "passive"))
    )
    (net (code "74") (name "Net-(J25-Pad7)") (class "Default")
      (node (ref "J25") (pin "7") (pinfunction "7_7") (pintype "passive"))
      (node (ref "R440") (pin "2") (pinfunction "2_2") (pintype "passive"))
    )
    (net (code "75") (name "Net-(J25-Pad8)") (class "Default")
      (node (ref "J25") (pin "8") (pinfunction "8_8") (pintype "passive"))
      (node (ref "R442") (pin "2") (pinfunction "2_2") (pintype "passive"))
    )
    (net (code "76") (name "Net-(J25-Pad9)") (class "Default")
      (node (ref "J25") (pin "9") (pinfunction "9_9") (pintype "passive"))
      (node (ref "R444") (pin "2") (pinfunction "2_2") (pintype "passive"))
    )
    (net (code "77") (name "Net-(J25-Pad10)") (class "Default")
      (node (ref "J25") (pin "10") (pinfunction "10_10") (pintype "passive"))
      (node (ref "R446") (pin "2") (pinfunction "2_2") (pintype "passive"))
    )
    (net (code "78") (name "Net-(J25-Pad11)") (class "Default")
      (node (ref "J25") (pin "11") (pinfunction "11_11") (pintype "passive"))
      (node (ref "R448") (pin "2") (pinfunction "2_2") (pintype "passive"))
    )
    (net (code "79") (name "Net-(U41-~{EN})") (class "Default")
      (node (ref "R314") (pin "2") (pinfunction "2_2") (pintype "passive"))
      (node (ref "U41") (pin "17") (pinfunction "~{EN}_17") (pintype "input"))
    )
    (net (code "80") (name "Net-(U42-~{EN})") (class "Default")
      (node (ref "R422") (pin "2") (pinfunction "2_2") (pintype "passive"))
      (node (ref "U42") (pin "17") (pinfunction "~{EN}_17") (pintype "input"))
    )
    (net (code "81") (name "Net-(U43-~{EN})") (class "Default")
      (node (ref "R449") (pin "2") (pinfunction "2_2") (pintype "passive"))
      (node (ref "U43") (pin "17") (pinfunction "~{EN}_17") (pintype "input"))
    )
    (net (code "82") (name "PHOTO_ADC_CONV") (class "Default")
      (node (ref "U41") (pin "9") (pinfunction "COM6_9") (pintype "passive"))
    )
    (net (code "83") (name "PHOTO_ADC_CS") (class "Default")
      (node (ref "U41") (pin "7") (pinfunction "COM5_7") (pintype "passive"))
    )
    (net (code "84") (name "PHOTO_ADC_EOC") (class "Default")
      (node (ref "U42") (pin "1") (pinfunction "COM1_1") (pintype "passive"))
    )
    (net (code "85") (name "PHOTO_CHOSE") (class "Default")
      (node (ref "R174") (pin "2") (pinfunction "2_2") (pintype "passive"))
      (node (ref "U41") (pin "11") (pinfunction "IN2_11") (pintype "input"))
      (node (ref "U41") (pin "21") (pinfunction "IN1_21") (pintype "input"))
      (node (ref "U42") (pin "21") (pinfunction "IN1_21") (pintype "input"))
    )
    (net (code "86") (name "PHOTO_SPI0_nCS2") (class "Default")
      (node (ref "U41") (pin "6") (pinfunction "COM4_6") (pintype "passive"))
    )
    (net (code "87") (name "unconnected-(U41-NC-Pad24)") (class "Default")
      (node (ref "U41") (pin "24") (pinfunction "NC_24") (pintype "passive+no_connect"))
    )
    (net (code "88") (name "unconnected-(U42-COM2-Pad3)") (class "Default")
      (node (ref "U42") (pin "3") (pinfunction "COM2_3") (pintype "passive"))
    )
    (net (code "89") (name "unconnected-(U42-COM3-Pad4)") (class "Default")
      (node (ref "U42") (pin "4") (pinfunction "COM3_4") (pintype "passive"))
    )
    (net (code "90") (name "unconnected-(U42-NC-Pad24)") (class "Default")
      (node (ref "U42") (pin "24") (pinfunction "NC_24") (pintype "passive+no_connect"))
    )
    (net (code "91") (name "unconnected-(U42-NC2-Pad22)") (class "Default")
      (node (ref "U42") (pin "22") (pinfunction "NC2_22") (pintype "passive"))
    )
    (net (code "92") (name "unconnected-(U42-NC3-Pad20)") (class "Default")
      (node (ref "U42") (pin "20") (pinfunction "NC3_20") (pintype "passive"))
    )
    (net (code "93") (name "unconnected-(U42-NO2-Pad10)") (class "Default")
      (node (ref "U42") (pin "10") (pinfunction "NO2_10") (pintype "passive"))
    )
    (net (code "94") (name "unconnected-(U42-NO3-Pad12)") (class "Default")
      (node (ref "U42") (pin "12") (pinfunction "NO3_12") (pintype "passive"))
    )
    (net (code "95") (name "unconnected-(U43-NC-Pad24)") (class "Default")
      (node (ref "U43") (pin "24") (pinfunction "NC_24") (pintype "passive+no_connect"))
    )
  )
)
